# circuit_layout.net
KiCad netlist of a schematic drawn in EAGLE
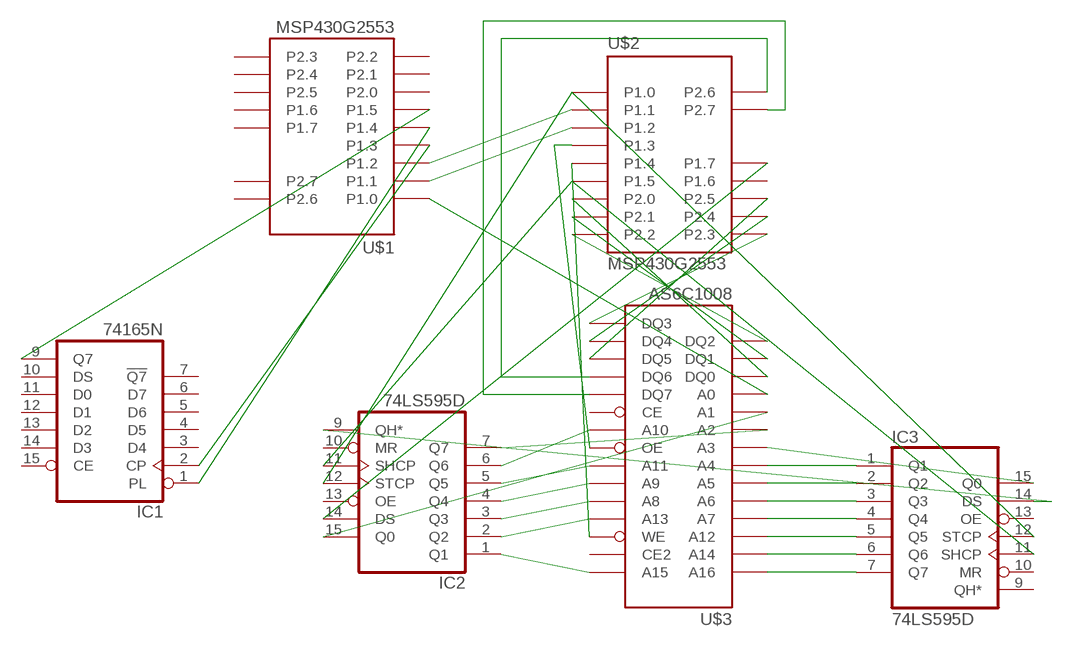
[diagram p0: schematic, sheet 1]

(export (version "E")
  (design (tool "Eeschema 10.0.6"))
  (components
    (comp (ref "IC1")
      (value "74165N")
      (footprint "eagle-import:DIL16")
      (libsource (lib "eagle-import") (part "74165N"))
    )
    (comp (ref "IC2")
      (value "74LS595D")
      (footprint "eagle-import:SO16")
      (libsource (lib "eagle-import") (part "74595DLS"))
    )
    (comp (ref "IC3")
      (value "74LS595D")
      (footprint "eagle-import:SO16")
      (libsource (lib "eagle-import") (part "74595DLS"))
    )
    (comp (ref "U$1")
      (value "MSP430G2553")
      (footprint "eagle-import:MSP430G2553")
      (libsource (lib "eagle-import") (part "MSP430G2553"))
    )
    (comp (ref "U$2")
      (value "MSP430G2553")
      (footprint "eagle-import:MSP430G2553")
      (libsource (lib "eagle-import") (part "MSP430G2553"))
    )
    (comp (ref "U$3")
      (value "AS6C1008")
      (footprint "eagle-import:AS6C1008")
      (libsource (lib "eagle-import") (part "AS6C1008"))
    )
  )
  (nets
    (net (code "1") (name "Net-(IC1A-CP)") (class "Default")
      (node (ref "IC1") (pin "2") (pinfunction "CP_2") (pintype "input"))
      (node (ref "U$1") (pin "P$4") (pinfunction "P1.3_P$4") (pintype "bidirectional"))
    )
    (net (code "2") (name "Net-(IC1A-PL)") (class "Default")
      (node (ref "IC1") (pin "1") (pinfunction "PL_1") (pintype "input"))
      (node (ref "U$1") (pin "P$5") (pinfunction "P1.4_P$5") (pintype "bidirectional"))
    )
    (net (code "3") (name "Net-(IC1A-Q7)") (class "Default")
      (node (ref "IC1") (pin "9") (pinfunction "Q7_9") (pintype "output"))
      (node (ref "U$1") (pin "P$6") (pinfunction "P1.5_P$6") (pintype "bidirectional"))
    )
    (net (code "4") (name "Net-(IC2A-DS)") (class "Default")
      (node (ref "IC2") (pin "14") (pinfunction "DS_14") (pintype "input"))
      (node (ref "U$2") (pin "P$8") (pinfunction "P1.7_P$8") (pintype "bidirectional"))
    )
    (net (code "5") (name "Net-(IC2A-Q0)") (class "Default")
      (node (ref "IC2") (pin "15") (pinfunction "Q0_15") (pintype "tri_state"))
      (node (ref "U$3") (pin "P$2") (pinfunction "A1_P$2") (pintype "bidirectional"))
    )
    (net (code "6") (name "Net-(IC2A-Q1)") (class "Default")
      (node (ref "IC2") (pin "1") (pinfunction "Q1_1") (pintype "tri_state"))
      (node (ref "U$3") (pin "P$16") (pinfunction "A15_P$16") (pintype "bidirectional"))
    )
    (net (code "7") (name "Net-(IC2A-Q2)") (class "Default")
      (node (ref "IC2") (pin "2") (pinfunction "Q2_2") (pintype "tri_state"))
      (node (ref "U$3") (pin "P$14") (pinfunction "A13_P$14") (pintype "bidirectional"))
    )
    (net (code "8") (name "Net-(IC2A-Q3)") (class "Default")
      (node (ref "IC2") (pin "3") (pinfunction "Q3_3") (pintype "tri_state"))
      (node (ref "U$3") (pin "P$9") (pinfunction "A8_P$9") (pintype "bidirectional"))
    )
    (net (code "9") (name "Net-(IC2A-Q4)") (class "Default")
      (node (ref "IC2") (pin "4") (pinfunction "Q4_4") (pintype "tri_state"))
      (node (ref "U$3") (pin "P$10") (pinfunction "A9_P$10") (pintype "bidirectional"))
    )
    (net (code "10") (name "Net-(IC2A-Q5)") (class "Default")
      (node (ref "IC2") (pin "5") (pinfunction "Q5_5") (pintype "tri_state"))
      (node (ref "U$3") (pin "P$12") (pinfunction "A11_P$12") (pintype "bidirectional"))
    )
    (net (code "11") (name "Net-(IC2A-Q6)") (class "Default")
      (node (ref "IC2") (pin "6") (pinfunction "Q6_6") (pintype "tri_state"))
      (node (ref "U$3") (pin "P$11") (pinfunction "A10_P$11") (pintype "bidirectional"))
    )
    (net (code "12") (name "Net-(IC2A-Q7)") (class "Default")
      (node (ref "IC2") (pin "7") (pinfunction "Q7_7") (pintype "tri_state"))
      (node (ref "U$3") (pin "P$3") (pinfunction "A2_P$3") (pintype "bidirectional"))
    )
    (net (code "13") (name "Net-(IC2A-QH*)") (class "Default")
      (node (ref "IC2") (pin "9") (pinfunction "QH*_9") (pintype "tri_state"))
      (node (ref "IC3") (pin "14") (pinfunction "DS_14") (pintype "input"))
    )
    (net (code "14") (name "Net-(IC2A-SHCP)") (class "Default")
      (node (ref "IC2") (pin "11") (pinfunction "SHCP_11") (pintype "input"))
      (node (ref "IC3") (pin "11") (pinfunction "SHCP_11") (pintype "input"))
      (node (ref "U$2") (pin "P$6") (pinfunction "P1.5_P$6") (pintype "bidirectional"))
    )
    (net (code "15") (name "Net-(IC2A-STCP)") (class "Default")
      (node (ref "IC2") (pin "12") (pinfunction "STCP_12") (pintype "input"))
      (node (ref "IC3") (pin "12") (pinfunction "STCP_12") (pintype "input"))
      (node (ref "U$2") (pin "P$1") (pinfunction "P1.0_P$1") (pintype "bidirectional"))
    )
    (net (code "16") (name "Net-(IC3A-Q0)") (class "Default")
      (node (ref "IC3") (pin "15") (pinfunction "Q0_15") (pintype "tri_state"))
      (node (ref "U$3") (pin "P$4") (pinfunction "A3_P$4") (pintype "bidirectional"))
    )
    (net (code "17") (name "Net-(IC3A-Q1)") (class "Default")
      (node (ref "IC3") (pin "1") (pinfunction "Q1_1") (pintype "tri_state"))
      (node (ref "U$3") (pin "P$5") (pinfunction "A4_P$5") (pintype "bidirectional"))
    )
    (net (code "18") (name "Net-(IC3A-Q2)") (class "Default")
      (node (ref "IC3") (pin "2") (pinfunction "Q2_2") (pintype "tri_state"))
      (node (ref "U$3") (pin "P$6") (pinfunction "A5_P$6") (pintype "bidirectional"))
    )
    (net (code "19") (name "Net-(IC3A-Q3)") (class "Default")
      (node (ref "IC3") (pin "3") (pinfunction "Q3_3") (pintype "tri_state"))
      (node (ref "U$3") (pin "P$7") (pinfunction "A6_P$7") (pintype "bidirectional"))
    )
    (net (code "20") (name "Net-(IC3A-Q4)") (class "Default")
      (node (ref "IC3") (pin "4") (pinfunction "Q4_4") (pintype "tri_state"))
      (node (ref "U$3") (pin "P$8") (pinfunction "A7_P$8") (pintype "bidirectional"))
    )
    (net (code "21") (name "Net-(IC3A-Q5)") (class "Default")
      (node (ref "IC3") (pin "5") (pinfunction "Q5_5") (pintype "tri_state"))
      (node (ref "U$3") (pin "P$13") (pinfunction "A12_P$13") (pintype "bidirectional"))
    )
    (net (code "22") (name "Net-(IC3A-Q6)") (class "Default")
      (node (ref "IC3") (pin "6") (pinfunction "Q6_6") (pintype "tri_state"))
      (node (ref "U$3") (pin "P$15") (pinfunction "A14_P$15") (pintype "bidirectional"))
    )
    (net (code "23") (name "Net-(IC3A-Q7)") (class "Default")
      (node (ref "IC3") (pin "7") (pinfunction "Q7_7") (pintype "tri_state"))
      (node (ref "U$3") (pin "P$17") (pinfunction "A16_P$17") (pintype "bidirectional"))
    )
    (net (code "24") (name "Net-(U$1-P1.0)") (class "Default")
      (node (ref "U$1") (pin "P$1") (pinfunction "P1.0_P$1") (pintype "bidirectional"))
      (node (ref "U$3") (pin "P$1") (pinfunction "A0_P$1") (pintype "bidirectional"))
    )
    (net (code "25") (name "Net-(U$1-P1.1)") (class "Default")
      (node (ref "U$1") (pin "P$2") (pinfunction "P1.1_P$2") (pintype "bidirectional"))
      (node (ref "U$2") (pin "P$3") (pinfunction "P1.2_P$3") (pintype "bidirectional"))
    )
    (net (code "26") (name "Net-(U$1-P1.2)") (class "Default")
      (node (ref "U$1") (pin "P$3") (pinfunction "P1.2_P$3") (pintype "bidirectional"))
      (node (ref "U$2") (pin "P$2") (pinfunction "P1.1_P$2") (pintype "bidirectional"))
    )
    (net (code "27") (name "Net-(U$2-P1.3)") (class "Default")
      (node (ref "U$2") (pin "P$4") (pinfunction "P1.3_P$4") (pintype "bidirectional"))
      (node (ref "U$3") (pin "P$28") (pinfunction "OE_P$28") (pintype "bidirectional"))
    )
    (net (code "28") (name "Net-(U$2-P1.4)") (class "Default")
      (node (ref "U$2") (pin "P$5") (pinfunction "P1.4_P$5") (pintype "bidirectional"))
      (node (ref "U$3") (pin "P$29") (pinfunction "WE_P$29") (pintype "bidirectional"))
    )
    (net (code "29") (name "Net-(U$2-P2.0)") (class "Default")
      (node (ref "U$2") (pin "P$9") (pinfunction "P2.0_P$9") (pintype "bidirectional"))
      (node (ref "U$3") (pin "P$20") (pinfunction "DQ0_P$20") (pintype "bidirectional"))
    )
    (net (code "30") (name "Net-(U$2-P2.1)") (class "Default")
      (node (ref "U$2") (pin "P$10") (pinfunction "P2.1_P$10") (pintype "bidirectional"))
      (node (ref "U$3") (pin "P$21") (pinfunction "DQ1_P$21") (pintype "bidirectional"))
    )
    (net (code "31") (name "Net-(U$2-P2.2)") (class "Default")
      (node (ref "U$2") (pin "P$11") (pinfunction "P2.2_P$11") (pintype "bidirectional"))
      (node (ref "U$3") (pin "P$22") (pinfunction "DQ2_P$22") (pintype "bidirectional"))
    )
    (net (code "32") (name "Net-(U$2-P2.3)") (class "Default")
      (node (ref "U$2") (pin "P$12") (pinfunction "P2.3_P$12") (pintype "bidirectional"))
      (node (ref "U$3") (pin "P$23") (pinfunction "DQ3_P$23") (pintype "bidirectional"))
    )
    (net (code "33") (name "Net-(U$2-P2.4)") (class "Default")
      (node (ref "U$2") (pin "P$13") (pinfunction "P2.4_P$13") (pintype "bidirectional"))
      (node (ref "U$3") (pin "P$24") (pinfunction "DQ4_P$24") (pintype "bidirectional"))
    )
    (net (code "34") (name "Net-(U$2-P2.5)") (class "Default")
      (node (ref "U$2") (pin "P$14") (pinfunction "P2.5_P$14") (pintype "bidirectional"))
      (node (ref "U$3") (pin "P$25") (pinfunction "DQ5_P$25") (pintype "bidirectional"))
    )
    (net (code "35") (name "Net-(U$2-P2.6)") (class "Default")
      (node (ref "U$2") (pin "P$15") (pinfunction "P2.6_P$15") (pintype "bidirectional"))
      (node (ref "U$3") (pin "P$26") (pinfunction "DQ6_P$26") (pintype "bidirectional"))
    )
    (net (code "36") (name "Net-(U$2-P2.7)") (class "Default")
      (node (ref "U$2") (pin "P$16") (pinfunction "P2.7_P$16") (pintype "bidirectional"))
      (node (ref "U$3") (pin "P$27") (pinfunction "DQ7_P$27") (pintype "bidirectional"))
    )
    (net (code "37") (name "unconnected-(IC1A-CE-Pad15)") (class "Default")
      (node (ref "IC1") (pin "15") (pinfunction "CE_15") (pintype "input"))
    )
    (net (code "38") (name "unconnected-(IC1A-D0-Pad11)") (class "Default")
      (node (ref "IC1") (pin "11") (pinfunction "D0_11") (pintype "input"))
    )
    (net (code "39") (name "unconnected-(IC1A-D1-Pad12)") (class "Default")
      (node (ref "IC1") (pin "12") (pinfunction "D1_12") (pintype "input"))
    )
    (net (code "40") (name "unconnected-(IC1A-D2-Pad13)") (class "Default")
      (node (ref "IC1") (pin "13") (pinfunction "D2_13") (pintype "input"))
    )
    (net (code "41") (name "unconnected-(IC1A-D3-Pad14)") (class "Default")
      (node (ref "IC1") (pin "14") (pinfunction "D3_14") (pintype "input"))
    )
    (net (code "42") (name "unconnected-(IC1A-D4-Pad3)") (class "Default")
      (node (ref "IC1") (pin "3") (pinfunction "D4_3") (pintype "input"))
    )
    (net (code "43") (name "unconnected-(IC1A-D5-Pad4)") (class "Default")
      (node (ref "IC1") (pin "4") (pinfunction "D5_4") (pintype "input"))
    )
    (net (code "44") (name "unconnected-(IC1A-D6-Pad5)") (class "Default")
      (node (ref "IC1") (pin "5") (pinfunction "D6_5") (pintype "input"))
    )
    (net (code "45") (name "unconnected-(IC1A-D7-Pad6)") (class "Default")
      (node (ref "IC1") (pin "6") (pinfunction "D7_6") (pintype "input"))
    )
    (net (code "46") (name "unconnected-(IC1A-DS-Pad10)") (class "Default")
      (node (ref "IC1") (pin "10") (pinfunction "DS_10") (pintype "input"))
    )
    (net (code "47") (name "unconnected-(IC1A-~{Q7}-Pad7)") (class "Default")
      (node (ref "IC1") (pin "7") (pinfunction "~{Q7}_7") (pintype "output"))
    )
    (net (code "48") (name "unconnected-(IC2A-MR-Pad10)") (class "Default")
      (node (ref "IC2") (pin "10") (pinfunction "MR_10") (pintype "input"))
    )
    (net (code "49") (name "unconnected-(IC2A-OE-Pad13)") (class "Default")
      (node (ref "IC2") (pin "13") (pinfunction "OE_13") (pintype "input"))
    )
    (net (code "50") (name "unconnected-(IC3A-MR-Pad10)") (class "Default")
      (node (ref "IC3") (pin "10") (pinfunction "MR_10") (pintype "input"))
    )
    (net (code "51") (name "unconnected-(IC3A-OE-Pad13)") (class "Default")
      (node (ref "IC3") (pin "13") (pinfunction "OE_13") (pintype "input"))
    )
    (net (code "52") (name "unconnected-(IC3A-QH*-Pad9)") (class "Default")
      (node (ref "IC3") (pin "9") (pinfunction "QH*_9") (pintype "tri_state"))
    )
    (net (code "53") (name "unconnected-(U$1-P1.6-PadP$7)") (class "Default")
      (node (ref "U$1") (pin "P$7") (pinfunction "P1.6_P$7") (pintype "bidirectional"))
    )
    (net (code "54") (name "unconnected-(U$1-P1.7-PadP$8)") (class "Default")
      (node (ref "U$1") (pin "P$8") (pinfunction "P1.7_P$8") (pintype "bidirectional"))
    )
    (net (code "55") (name "unconnected-(U$1-P2.0-PadP$9)") (class "Default")
      (node (ref "U$1") (pin "P$9") (pinfunction "P2.0_P$9") (pintype "bidirectional"))
    )
    (net (code "56") (name "unconnected-(U$1-P2.1-PadP$10)") (class "Default")
      (node (ref "U$1") (pin "P$10") (pinfunction "P2.1_P$10") (pintype "bidirectional"))
    )
    (net (code "57") (name "unconnected-(U$1-P2.2-PadP$11)") (class "Default")
      (node (ref "U$1") (pin "P$11") (pinfunction "P2.2_P$11") (pintype "bidirectional"))
    )
    (net (code "58") (name "unconnected-(U$1-P2.3-PadP$12)") (class "Default")
      (node (ref "U$1") (pin "P$12") (pinfunction "P2.3_P$12") (pintype "bidirectional"))
    )
    (net (code "59") (name "unconnected-(U$1-P2.4-PadP$13)") (class "Default")
      (node (ref "U$1") (pin "P$13") (pinfunction "P2.4_P$13") (pintype "bidirectional"))
    )
    (net (code "60") (name "unconnected-(U$1-P2.5-PadP$14)") (class "Default")
      (node (ref "U$1") (pin "P$14") (pinfunction "P2.5_P$14") (pintype "bidirectional"))
    )
    (net (code "61") (name "unconnected-(U$1-P2.6-PadP$15)") (class "Default")
      (node (ref "U$1") (pin "P$15") (pinfunction "P2.6_P$15") (pintype "bidirectional"))
    )
    (net (code "62") (name "unconnected-(U$1-P2.7-PadP$16)") (class "Default")
      (node (ref "U$1") (pin "P$16") (pinfunction "P2.7_P$16") (pintype "bidirectional"))
    )
    (net (code "63") (name "unconnected-(U$2-P1.6-PadP$7)") (class "Default")
      (node (ref "U$2") (pin "P$7") (pinfunction "P1.6_P$7") (pintype "bidirectional"))
    )
    (net (code "64") (name "unconnected-(U$3-CE-PadP$18)") (class "Default")
      (node (ref "U$3") (pin "P$18") (pinfunction "CE_P$18") (pintype "bidirectional"))
    )
    (net (code "65") (name "unconnected-(U$3-CE2-PadP$19)") (class "Default")
      (node (ref "U$3") (pin "P$19") (pinfunction "CE2_P$19") (pintype "bidirectional"))
    )
  )
)
